# HandHeld_Terminal_V2.net
KiCad netlist of a schematic drawn in Altium Designer
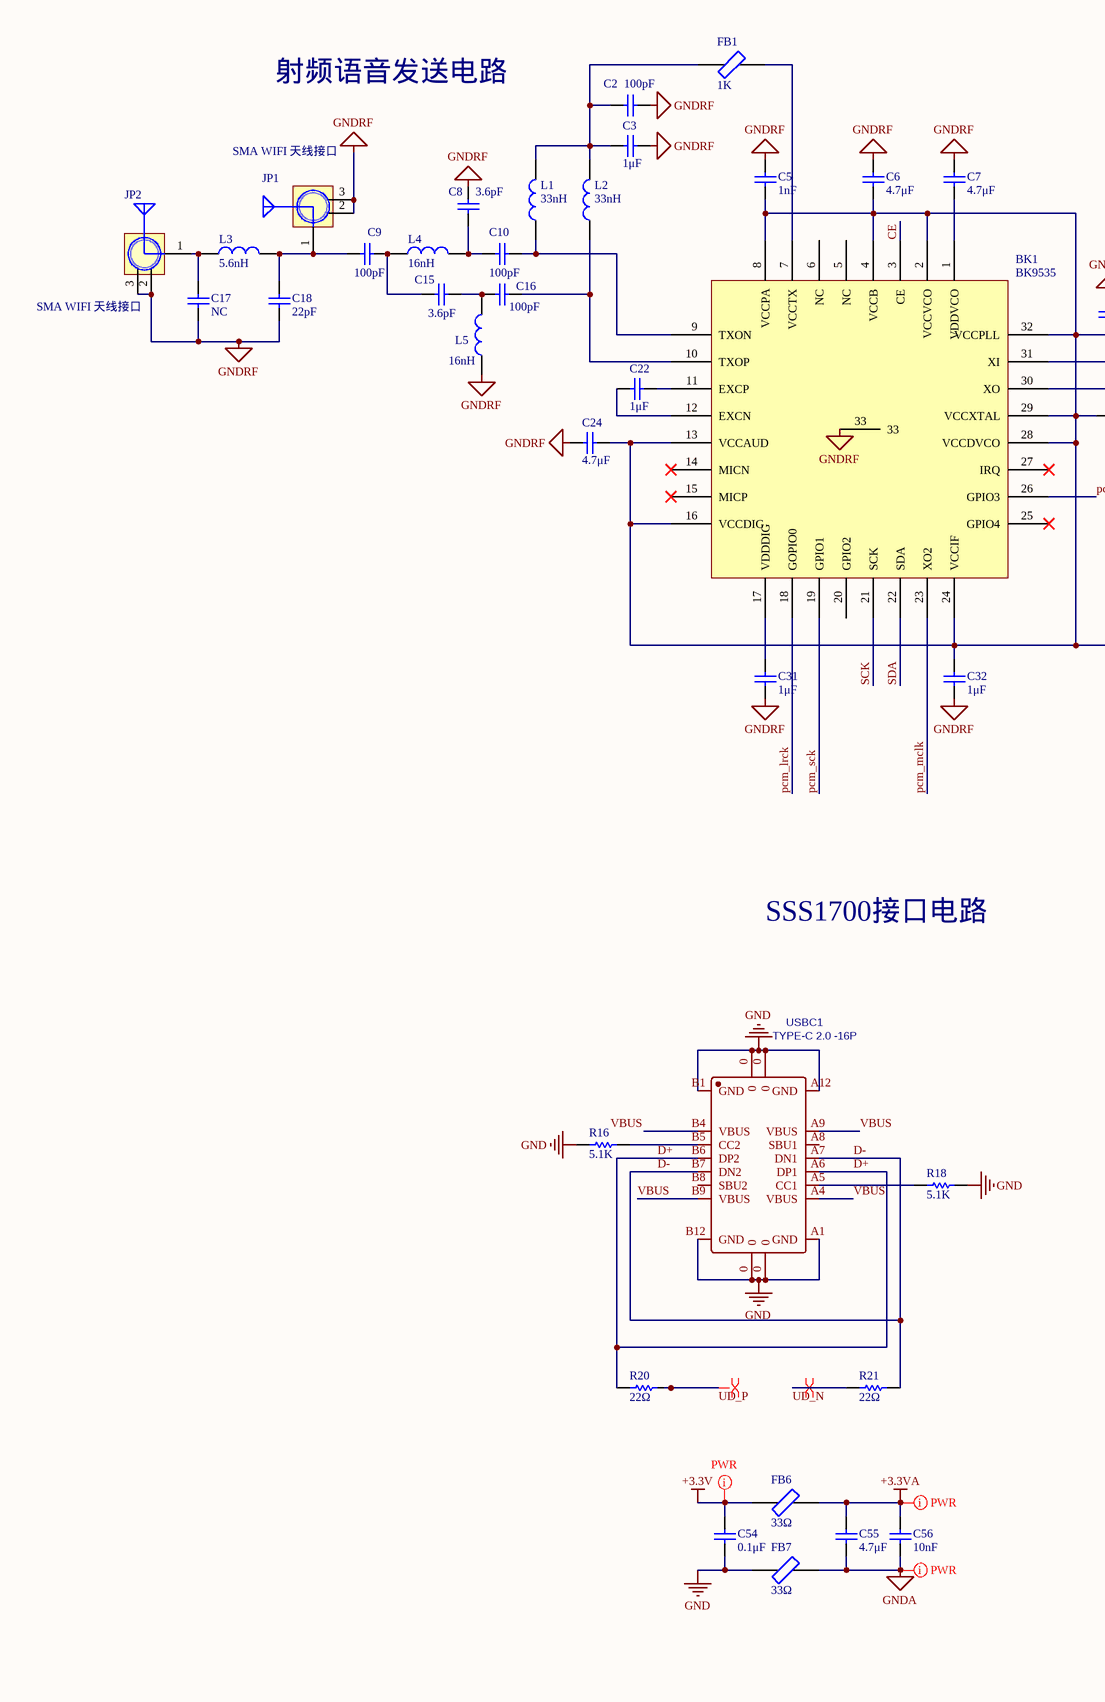
[diagram p0: HandHeld_Terminal_V2.SchDoc, left]
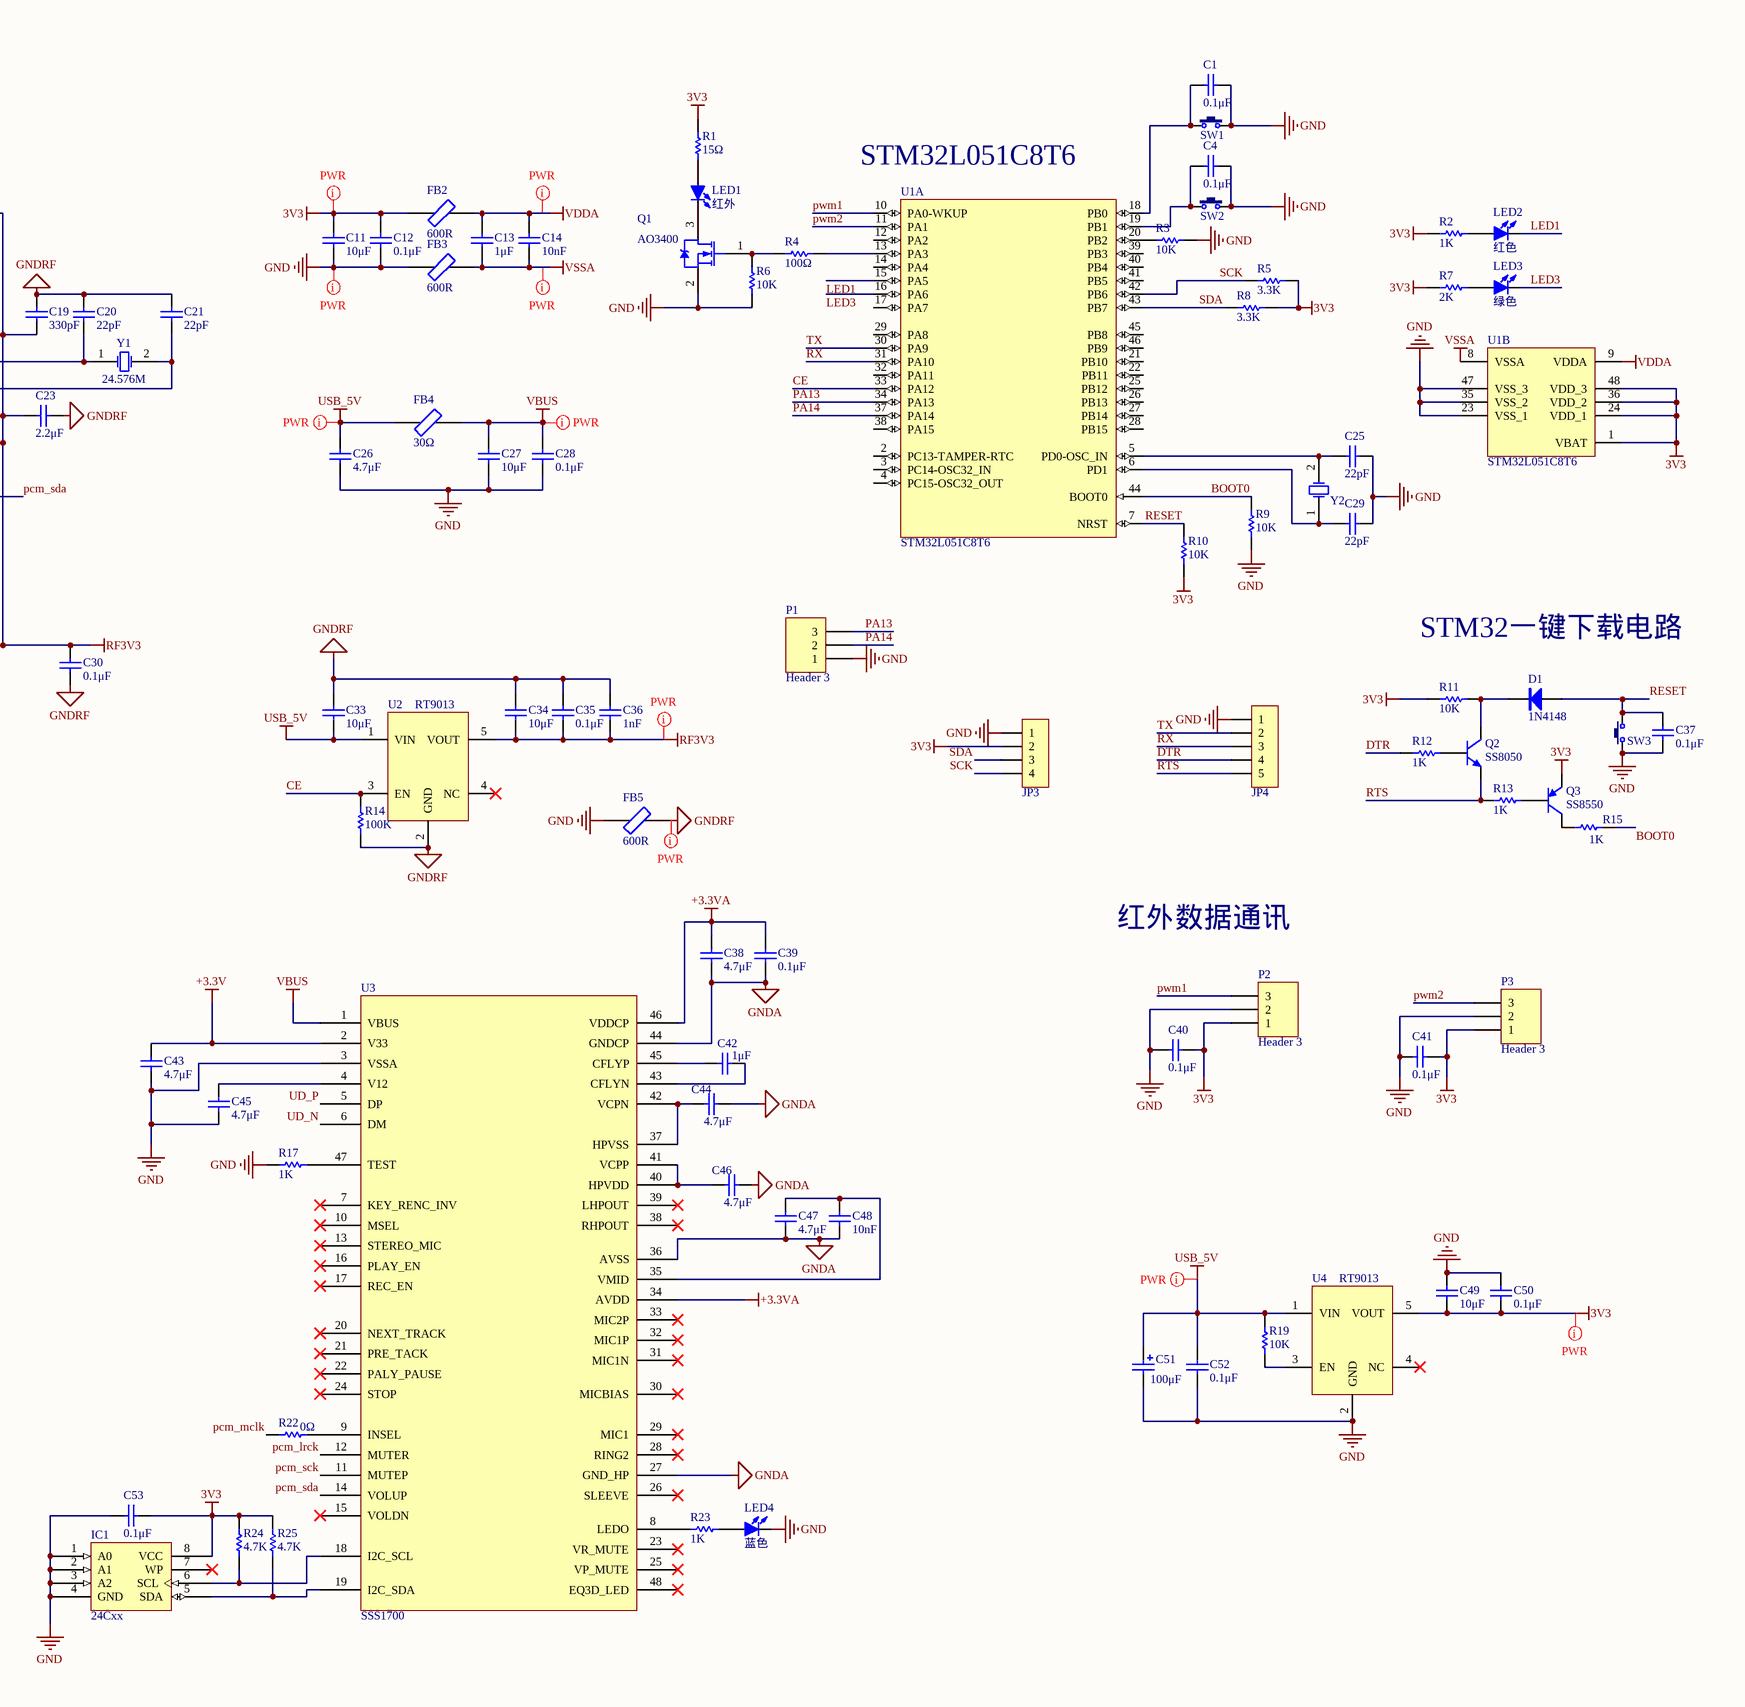
[diagram p1: HandHeld_Terminal_V2.SchDoc, right]

(export (version "E")
  (design (tool "Eeschema 10.0.6"))
  (components
    (comp (ref "BK1") (value "BK9535") (footprint "QFN32 5x5_N") (libsource (lib "Nixie") (part "BK9530")))
    (comp (ref "C1")
      (value "0.1μF")
      (footprint "C 0603_L")
      (description "Capacitor")
      (fields (field (name "Comment") "Cap") (field (name "PUBLISHER") "Altium Limited"))
      (libsource (lib "Nixie") (part "Cap"))
    )
    (comp (ref "C2")
      (value "100pF")
      (footprint "C 0603_L")
      (description "Capacitor")
      (fields (field (name "Comment") "Cap") (field (name "PUBLISHER") "Altium Limited"))
      (libsource (lib "Nixie") (part "Cap"))
    )
    (comp (ref "C3")
      (value "1μF")
      (footprint "C 0603_L")
      (description "Capacitor")
      (fields (field (name "Comment") "Cap") (field (name "PUBLISHER") "Altium Limited"))
      (libsource (lib "Nixie") (part "Cap"))
    )
    (comp (ref "C4")
      (value "0.1μF")
      (footprint "C 0603_L")
      (description "Capacitor")
      (fields (field (name "Comment") "Cap") (field (name "PUBLISHER") "Altium Limited"))
      (libsource (lib "Nixie") (part "Cap"))
    )
    (comp (ref "C5")
      (value "1nF")
      (footprint "C 0603_L")
      (description "Capacitor")
      (fields (field (name "Comment") "Cap") (field (name "PUBLISHER") "Altium Limited"))
      (libsource (lib "Nixie") (part "Cap"))
    )
    (comp (ref "C6")
      (value "4.7μF")
      (footprint "C 0603_L")
      (description "Capacitor")
      (fields (field (name "Comment") "Cap") (field (name "PUBLISHER") "Altium Limited"))
      (libsource (lib "Nixie") (part "Cap"))
    )
    (comp (ref "C7")
      (value "4.7μF")
      (footprint "C 0603_L")
      (description "Capacitor")
      (fields (field (name "Comment") "Cap") (field (name "PUBLISHER") "Altium Limited"))
      (libsource (lib "Nixie") (part "Cap"))
    )
    (comp (ref "C8")
      (value "3.6pF")
      (footprint "C 0603_L")
      (description "Capacitor")
      (fields (field (name "Comment") "Cap") (field (name "PUBLISHER") "Altium Limited"))
      (libsource (lib "Nixie") (part "Cap"))
    )
    (comp (ref "C9")
      (value "100pF")
      (footprint "C 0603_L")
      (description "Capacitor")
      (fields (field (name "Comment") "Cap") (field (name "PUBLISHER") "Altium Limited"))
      (libsource (lib "Nixie") (part "Cap"))
    )
    (comp (ref "C10")
      (value "100pF")
      (footprint "C 0603_L")
      (description "Capacitor")
      (fields (field (name "Comment") "Cap") (field (name "PUBLISHER") "Altium Limited"))
      (libsource (lib "Nixie") (part "Cap"))
    )
    (comp (ref "C11")
      (value "10μF")
      (footprint "C 0805_L")
      (description "Capacitor")
      (fields (field (name "Comment") "Cap") (field (name "PUBLISHER") "Altium Limited"))
      (libsource (lib "Nixie") (part "Cap"))
    )
    (comp (ref "C12")
      (value "0.1μF")
      (footprint "C 0603_L")
      (description "Capacitor")
      (fields (field (name "Comment") "Cap") (field (name "PUBLISHER") "Altium Limited"))
      (libsource (lib "Nixie") (part "Cap"))
    )
    (comp (ref "C13")
      (value "1μF")
      (footprint "C 0805_L")
      (description "Capacitor")
      (fields (field (name "Comment") "Cap") (field (name "PUBLISHER") "Altium Limited"))
      (libsource (lib "Nixie") (part "Cap"))
    )
    (comp (ref "C14")
      (value "10nF")
      (footprint "C 0805_L")
      (description "Capacitor")
      (fields (field (name "Comment") "Cap") (field (name "PUBLISHER") "Altium Limited"))
      (libsource (lib "Nixie") (part "Cap"))
    )
    (comp (ref "C15")
      (value "3.6pF")
      (footprint "C 0603_L")
      (description "Capacitor")
      (fields (field (name "Comment") "Cap") (field (name "PUBLISHER") "Altium Limited"))
      (libsource (lib "Nixie") (part "Cap"))
    )
    (comp (ref "C16")
      (value "100pF")
      (footprint "C 0603_L")
      (description "Capacitor")
      (fields (field (name "Comment") "Cap") (field (name "PUBLISHER") "Altium Limited"))
      (libsource (lib "Nixie") (part "Cap"))
    )
    (comp (ref "C17")
      (value "NC")
      (footprint "C 0603_L")
      (description "Capacitor")
      (fields (field (name "Comment") "Cap") (field (name "PUBLISHER") "Altium Limited"))
      (libsource (lib "Nixie") (part "Cap"))
    )
    (comp (ref "C18")
      (value "22pF")
      (footprint "C 0603_L")
      (description "Capacitor")
      (fields (field (name "Comment") "Cap") (field (name "PUBLISHER") "Altium Limited"))
      (libsource (lib "Nixie") (part "Cap"))
    )
    (comp (ref "C19")
      (value "330pF")
      (footprint "C 0603_L")
      (description "Capacitor")
      (fields (field (name "Comment") "Cap") (field (name "PUBLISHER") "Altium Limited"))
      (libsource (lib "Nixie") (part "Cap"))
    )
    (comp (ref "C20")
      (value "22pF")
      (footprint "C 0603_L")
      (description "Capacitor")
      (fields (field (name "Comment") "Cap") (field (name "PUBLISHER") "Altium Limited"))
      (libsource (lib "Nixie") (part "Cap"))
    )
    (comp (ref "C21")
      (value "22pF")
      (footprint "C 0603_L")
      (description "Capacitor")
      (fields (field (name "Comment") "Cap") (field (name "PUBLISHER") "Altium Limited"))
      (libsource (lib "Nixie") (part "Cap"))
    )
    (comp (ref "C22")
      (value "1μF")
      (footprint "C 0603_L")
      (description "Capacitor")
      (fields (field (name "Comment") "Cap") (field (name "PUBLISHER") "Altium Limited"))
      (libsource (lib "Nixie") (part "Cap"))
    )
    (comp (ref "C23")
      (value "2.2μF")
      (footprint "C 0603_L")
      (description "Capacitor")
      (fields (field (name "Comment") "Cap") (field (name "PUBLISHER") "Altium Limited"))
      (libsource (lib "Nixie") (part "Cap"))
    )
    (comp (ref "C24")
      (value "4.7μF")
      (footprint "C 0603_L")
      (description "Capacitor")
      (fields (field (name "Comment") "Cap") (field (name "PUBLISHER") "Altium Limited"))
      (libsource (lib "Nixie") (part "Cap"))
    )
    (comp (ref "C25")
      (value "22pF")
      (footprint "C 0603_L")
      (description "Capacitor")
      (fields (field (name "Comment") "Cap") (field (name "PUBLISHER") "Altium Limited"))
      (libsource (lib "Nixie") (part "Cap"))
    )
    (comp (ref "C26")
      (value "4.7μF")
      (footprint "C 0805_L")
      (description "Capacitor")
      (fields (field (name "Comment") "Cap") (field (name "PUBLISHER") "Altium Limited"))
      (libsource (lib "Nixie") (part "Cap"))
    )
    (comp (ref "C27")
      (value "10μF")
      (footprint "C 0805_L")
      (description "Capacitor")
      (fields (field (name "Comment") "Cap") (field (name "PUBLISHER") "Altium Limited"))
      (libsource (lib "Nixie") (part "Cap"))
    )
    (comp (ref "C28")
      (value "0.1μF")
      (footprint "C 0603_L")
      (description "Capacitor")
      (fields (field (name "Comment") "Cap") (field (name "PUBLISHER") "Altium Limited"))
      (libsource (lib "Nixie") (part "Cap"))
    )
    (comp (ref "C29")
      (value "22pF")
      (footprint "C 0603_L")
      (description "Capacitor")
      (fields (field (name "Comment") "Cap") (field (name "PUBLISHER") "Altium Limited"))
      (libsource (lib "Nixie") (part "Cap"))
    )
    (comp (ref "C30")
      (value "0.1μF")
      (footprint "C 0603_L")
      (description "Capacitor")
      (fields (field (name "Comment") "Cap") (field (name "PUBLISHER") "Altium Limited"))
      (libsource (lib "Nixie") (part "Cap"))
    )
    (comp (ref "C31")
      (value "1μF")
      (footprint "C 0603_L")
      (description "Capacitor")
      (fields (field (name "Comment") "Cap") (field (name "PUBLISHER") "Altium Limited"))
      (libsource (lib "Nixie") (part "Cap"))
    )
    (comp (ref "C32")
      (value "1μF")
      (footprint "C 0603_L")
      (description "Capacitor")
      (fields (field (name "Comment") "Cap") (field (name "PUBLISHER") "Altium Limited"))
      (libsource (lib "Nixie") (part "Cap"))
    )
    (comp (ref "C33")
      (value "10μF")
      (footprint "C 0805_L")
      (description "Capacitor")
      (fields (field (name "Comment") "Cap") (field (name "PUBLISHER") "Altium Limited"))
      (libsource (lib "Nixie") (part "Cap"))
    )
    (comp (ref "C34")
      (value "10μF")
      (footprint "C 0805_L")
      (description "Capacitor")
      (fields (field (name "Comment") "Cap") (field (name "PUBLISHER") "Altium Limited"))
      (libsource (lib "Nixie") (part "Cap"))
    )
    (comp (ref "C35")
      (value "0.1μF")
      (footprint "C 0603_L")
      (description "Capacitor")
      (fields (field (name "Comment") "Cap") (field (name "PUBLISHER") "Altium Limited"))
      (libsource (lib "Nixie") (part "Cap"))
    )
    (comp (ref "C36")
      (value "1nF")
      (footprint "C 0603_L")
      (description "Capacitor")
      (fields (field (name "Comment") "Cap") (field (name "PUBLISHER") "Altium Limited"))
      (libsource (lib "Nixie") (part "Cap"))
    )
    (comp (ref "C37")
      (value "0.1μF")
      (footprint "C 0603_L")
      (description "Capacitor")
      (fields (field (name "Comment") "Cap") (field (name "PUBLISHER") "Altium Limited"))
      (libsource (lib "Nixie") (part "Cap"))
    )
    (comp (ref "C38")
      (value "4.7μF")
      (footprint "C 0603_L")
      (description "Capacitor")
      (fields (field (name "Comment") "Cap") (field (name "PUBLISHER") "Altium Limited"))
      (libsource (lib "Nixie") (part "Cap"))
    )
    (comp (ref "C39")
      (value "0.1μF")
      (footprint "C 0603_L")
      (description "Capacitor")
      (fields (field (name "Comment") "Cap") (field (name "PUBLISHER") "Altium Limited"))
      (libsource (lib "Nixie") (part "Cap"))
    )
    (comp (ref "C40")
      (value "0.1μF")
      (footprint "C 0603_L")
      (description "Capacitor")
      (fields (field (name "Comment") "Cap") (field (name "PUBLISHER") "Altium Limited"))
      (libsource (lib "Nixie") (part "Cap"))
    )
    (comp (ref "C41")
      (value "0.1μF")
      (footprint "C 0603_L")
      (description "Capacitor")
      (fields (field (name "Comment") "Cap") (field (name "PUBLISHER") "Altium Limited"))
      (libsource (lib "Nixie") (part "Cap"))
    )
    (comp (ref "C42")
      (value "1μF")
      (footprint "C 0603_L")
      (description "Capacitor")
      (fields (field (name "Comment") "Cap") (field (name "PUBLISHER") "Altium Limited"))
      (libsource (lib "Nixie") (part "Cap"))
    )
    (comp (ref "C43")
      (value "4.7μF")
      (footprint "C 0603_L")
      (description "Capacitor")
      (fields (field (name "Comment") "Cap") (field (name "PUBLISHER") "Altium Limited"))
      (libsource (lib "Nixie") (part "Cap"))
    )
    (comp (ref "C44")
      (value "4.7μF")
      (footprint "C 0603_L")
      (description "Capacitor")
      (fields (field (name "Comment") "Cap") (field (name "PUBLISHER") "Altium Limited"))
      (libsource (lib "Nixie") (part "Cap"))
    )
    (comp (ref "C45")
      (value "4.7μF")
      (footprint "C 0603_L")
      (description "Capacitor")
      (fields (field (name "Comment") "Cap") (field (name "PUBLISHER") "Altium Limited"))
      (libsource (lib "Nixie") (part "Cap"))
    )
    (comp (ref "C46")
      (value "4.7μF")
      (footprint "C 0603_L")
      (description "Capacitor")
      (fields (field (name "Comment") "Cap") (field (name "PUBLISHER") "Altium Limited"))
      (libsource (lib "Nixie") (part "Cap"))
    )
    (comp (ref "C47")
      (value "4.7μF")
      (footprint "C 0603_L")
      (description "Capacitor")
      (fields (field (name "Comment") "Cap") (field (name "PUBLISHER") "Altium Limited"))
      (libsource (lib "Nixie") (part "Cap"))
    )
    (comp (ref "C48")
      (value "10nF")
      (footprint "C 0603_L")
      (description "Capacitor")
      (fields (field (name "Comment") "Cap") (field (name "PUBLISHER") "Altium Limited"))
      (libsource (lib "Nixie") (part "Cap"))
    )
    (comp (ref "C49")
      (value "10μF")
      (footprint "C 0805_L")
      (description "Capacitor")
      (fields (field (name "Comment") "Cap") (field (name "PUBLISHER") "Altium Limited"))
      (libsource (lib "Nixie") (part "Cap"))
    )
    (comp (ref "C50")
      (value "0.1μF")
      (footprint "C 0603_L")
      (description "Capacitor")
      (fields (field (name "Comment") "Cap") (field (name "PUBLISHER") "Altium Limited"))
      (libsource (lib "Nixie") (part "Cap"))
    )
    (comp (ref "C51")
      (value "100μF")
      (footprint "CM C(5*5.4)")
      (description "Polarized Capacitor (Radial)")
      (fields (field (name "Comment") "Cap Pol1") (field (name "PUBLISHER") "Altium Limited"))
      (libsource (lib "Nixie") (part "Cap Pol1"))
    )
    (comp (ref "C52")
      (value "0.1μF")
      (footprint "C 0603_L")
      (description "Capacitor")
      (fields (field (name "Comment") "Cap") (field (name "PUBLISHER") "Altium Limited"))
      (libsource (lib "Nixie") (part "Cap"))
    )
    (comp (ref "C53")
      (value "0.1μF")
      (footprint "C 0603_L")
      (description "Capacitor")
      (fields (field (name "Comment") "Cap") (field (name "PUBLISHER") "Altium Limited"))
      (libsource (lib "Nixie") (part "Cap"))
    )
    (comp (ref "C54")
      (value "0.1μF")
      (footprint "C 0603_L")
      (description "Capacitor")
      (fields (field (name "Comment") "Cap") (field (name "PUBLISHER") "Altium Limited"))
      (libsource (lib "Nixie") (part "Cap"))
    )
    (comp (ref "C55")
      (value "4.7μF")
      (footprint "C 0805_L")
      (description "Capacitor")
      (fields (field (name "Comment") "Cap") (field (name "PUBLISHER") "Altium Limited"))
      (libsource (lib "Nixie") (part "Cap"))
    )
    (comp (ref "C56")
      (value "10nF")
      (footprint "C 0603_L")
      (description "Capacitor")
      (fields (field (name "Comment") "Cap") (field (name "PUBLISHER") "Altium Limited"))
      (libsource (lib "Nixie") (part "Cap"))
    )
    (comp (ref "D1")
      (value "1N4148")
      (footprint "SOD-323")
      (description "开关二极管")
      (libsource (lib "Nixie") (part "1N4148"))
    )
    (comp (ref "FB1")
      (value "1K")
      (footprint "C 0603_L")
      (description "铁氧体磁珠")
      (fields (field (name "Comment") "Ferrite bead"))
      (libsource (lib "Nixie") (part "Ferrite bead"))
    )
    (comp (ref "FB2")
      (value "600R")
      (footprint "C 0603_L")
      (description "铁氧体磁珠")
      (fields (field (name "Comment") "Ferrite bead"))
      (libsource (lib "Nixie") (part "Ferrite bead"))
    )
    (comp (ref "FB3")
      (value "600R")
      (footprint "C 0603_L")
      (description "铁氧体磁珠")
      (fields (field (name "Comment") "Ferrite bead"))
      (libsource (lib "Nixie") (part "Ferrite bead"))
    )
    (comp (ref "FB4")
      (value "30Ω")
      (footprint "C 0603_L")
      (description "铁氧体磁珠")
      (fields (field (name "Comment") "Ferrite bead"))
      (libsource (lib "Nixie") (part "Ferrite bead"))
    )
    (comp (ref "FB5")
      (value "600R")
      (footprint "C 0805_L")
      (description "铁氧体磁珠")
      (fields (field (name "Comment") "Ferrite bead"))
      (libsource (lib "Nixie") (part "Ferrite bead"))
    )
    (comp (ref "FB6")
      (value "33Ω")
      (footprint "C 0603_L")
      (description "铁氧体磁珠")
      (fields (field (name "Comment") "Ferrite bead"))
      (libsource (lib "Nixie") (part "Ferrite bead"))
    )
    (comp (ref "FB7")
      (value "33Ω")
      (footprint "C 0603_L")
      (description "铁氧体磁珠")
      (fields (field (name "Comment") "Ferrite bead"))
      (libsource (lib "Nixie") (part "Ferrite bead"))
    )
    (comp (ref "IC1")
      (value "24Cxx")
      (footprint "SOP8_L")
      (description "外置EEPROM")
      (fields (field (name "版权归属") "封装库来自淘宝 ID：黄晶宝石"))
      (libsource (lib "Nixie") (part "24Cxx"))
    )
    (comp (ref "JP1")
      (value "SMA WIFI 天线接口")
      (footprint "COAXIAL/SMD/CON/V/I-PEX/W08-5801")
      (description "SMA-2.4G射频天线接口")
      (fields (field (name "版权归属") "封装库来自淘宝 ID：黄晶宝石"))
      (libsource (lib "Nixie") (part "SMA"))
    )
    (comp (ref "JP2")
      (value "SMA WIFI 天线接口")
      (footprint "SMA-KE")
      (description "SMA-2.4G射频天线接口")
      (fields (field (name "版权归属") "封装库来自淘宝 ID：黄晶宝石"))
      (libsource (lib "") (part "SMA_1"))
    )
    (comp (ref "JP3")
      (value "HDR-1X4")
      (footprint "HDR2.54-LI-4P")
      (description "4P接插件")
      (fields (field (name "版权归属") "封装库来自淘宝 ID：黄晶宝石"))
      (libsource (lib "Nixie") (part "Header 4"))
    )
    (comp (ref "JP4")
      (value "HDR-1X5")
      (footprint "HDR2.0-LI-5P")
      (description "5P接插件")
      (fields (field (name "版权归属") "封装库来自淘宝 ID：黄晶宝石"))
      (libsource (lib "Nixie") (part "Header 5"))
    )
    (comp (ref "L1")
      (value "33nH")
      (footprint "L 0603")
      (description "小功率贴片电感")
      (fields (field (name "Comment") "L"))
      (libsource (lib "Nixie") (part "L"))
    )
    (comp (ref "L2")
      (value "33nH")
      (footprint "L 0603")
      (description "小功率贴片电感")
      (fields (field (name "Comment") "L"))
      (libsource (lib "Nixie") (part "L"))
    )
    (comp (ref "L3")
      (value "5.6nH")
      (footprint "L 0603")
      (description "小功率贴片电感")
      (fields (field (name "Comment") "L"))
      (libsource (lib "Nixie") (part "L"))
    )
    (comp (ref "L4")
      (value "16nH")
      (footprint "L 0603")
      (description "小功率贴片电感")
      (fields (field (name "Comment") "L"))
      (libsource (lib "Nixie") (part "L"))
    )
    (comp (ref "L5")
      (value "16nH")
      (footprint "L 0603")
      (description "小功率贴片电感")
      (fields (field (name "Comment") "L"))
      (libsource (lib "Nixie") (part "L"))
    )
    (comp (ref "LED1")
      (value "红外")
      (footprint "LED 3MM-R")
      (description "贴片LED")
      (fields (field (name "版权归属") "封装库来自淘宝 ID：黄晶宝石"))
      (libsource (lib "Nixie") (part "LED-SMD"))
    )
    (comp (ref "LED2")
      (value "红色")
      (footprint "LED 0805R")
      (description "贴片LED")
      (fields (field (name "版权归属") "封装库来自淘宝 ID：黄晶宝石"))
      (libsource (lib "Nixie") (part "LED-SMD"))
    )
    (comp (ref "LED3")
      (value "绿色")
      (footprint "LED 0805G")
      (description "贴片LED")
      (fields (field (name "版权归属") "封装库来自淘宝 ID：黄晶宝石"))
      (libsource (lib "Nixie") (part "LED-SMD"))
    )
    (comp (ref "LED4")
      (value "蓝色")
      (footprint "LED 0805B")
      (description "贴片LED")
      (fields (field (name "版权归属") "封装库来自淘宝 ID：黄晶宝石"))
      (libsource (lib "Nixie") (part "LED-SMD"))
    )
    (comp (ref "P1")
      (value "Header 3")
      (footprint "HDR2.54-LI-3P")
      (description "Header, 3-Pin")
      (fields (field (name "PUBLISHER") "Altium Limited"))
      (libsource (lib "Miscellaneous Connectors") (part "Header 3"))
    )
    (comp (ref "P2")
      (value "Header 3")
      (footprint "HDR1X3")
      (description "Header, 3-Pin")
      (fields (field (name "PUBLISHER") "Altium Limited"))
      (libsource (lib "") (part "Header 3_1"))
    )
    (comp (ref "P3")
      (value "Header 3")
      (footprint "HDR1X3")
      (description "Header, 3-Pin")
      (fields (field (name "PUBLISHER") "Altium Limited"))
      (libsource (lib "") (part "Header 3_1"))
    )
    (comp (ref "Q1")
      (value "AO3400")
      (footprint "SOT-23-3L")
      (description "N-Channel Power MOSFET")
      (fields (field (name "PUBLISHER") "Altium Limited"))
      (libsource (lib "Nixie") (part "NMOS-2"))
    )
    (comp (ref "Q2")
      (value "SS8050")
      (footprint "SOT-23-3L")
      (description "高频放大-NPN型")
      (fields (field (name "版权归属") "封装库来自淘宝 ID：黄晶宝石"))
      (libsource (lib "Nixie") (part "8050-SMD"))
    )
    (comp (ref "Q3")
      (value "SS8550")
      (footprint "SOT-23-3L")
      (description "高频放大-PNP型")
      (fields (field (name "版权归属") "封装库来自淘宝 ID：黄晶宝石"))
      (libsource (lib "Nixie") (part "8550-SMD"))
    )
    (comp (ref "R1")
      (value "15Ω")
      (footprint "R 1206_L")
      (description "Resistor")
      (fields (field (name "PUBLISHER") "Altium Limited"))
      (libsource (lib "Nixie") (part "Resistor"))
    )
    (comp (ref "R2")
      (value "1K")
      (footprint "R 0603_L")
      (description "Resistor")
      (fields (field (name "PUBLISHER") "Altium Limited"))
      (libsource (lib "Nixie") (part "Resistor"))
    )
    (comp (ref "R3")
      (value "10K")
      (footprint "R 0603_L")
      (description "Resistor")
      (fields (field (name "PUBLISHER") "Altium Limited"))
      (libsource (lib "Nixie") (part "Resistor"))
    )
    (comp (ref "R4")
      (value "100Ω")
      (footprint "R 0603_L")
      (description "Resistor")
      (fields (field (name "PUBLISHER") "Altium Limited"))
      (libsource (lib "Nixie") (part "Resistor"))
    )
    (comp (ref "R5")
      (value "3.3K")
      (footprint "R 0603_L")
      (description "Resistor")
      (fields (field (name "PUBLISHER") "Altium Limited"))
      (libsource (lib "Nixie") (part "Resistor"))
    )
    (comp (ref "R6")
      (value "10K")
      (footprint "R 0603_L")
      (description "Resistor")
      (fields (field (name "PUBLISHER") "Altium Limited"))
      (libsource (lib "Nixie") (part "Resistor"))
    )
    (comp (ref "R7")
      (value "2K")
      (footprint "R 0603_L")
      (description "Resistor")
      (fields (field (name "PUBLISHER") "Altium Limited"))
      (libsource (lib "Nixie") (part "Resistor"))
    )
    (comp (ref "R8")
      (value "3.3K")
      (footprint "R 0603_L")
      (description "Resistor")
      (fields (field (name "PUBLISHER") "Altium Limited"))
      (libsource (lib "Nixie") (part "Resistor"))
    )
    (comp (ref "R9")
      (value "10K")
      (footprint "R 0603_L")
      (description "Resistor")
      (fields (field (name "PUBLISHER") "Altium Limited"))
      (libsource (lib "Nixie") (part "Resistor"))
    )
    (comp (ref "R10")
      (value "10K")
      (footprint "R 0603_L")
      (description "Resistor")
      (fields (field (name "PUBLISHER") "Altium Limited"))
      (libsource (lib "Nixie") (part "Resistor"))
    )
    (comp (ref "R11")
      (value "10K")
      (footprint "R 0603_L")
      (description "Resistor")
      (fields (field (name "PUBLISHER") "Altium Limited"))
      (libsource (lib "Nixie") (part "Resistor"))
    )
    (comp (ref "R12")
      (value "1K")
      (footprint "R 0603_L")
      (description "Resistor")
      (fields (field (name "PUBLISHER") "Altium Limited"))
      (libsource (lib "Nixie") (part "Resistor"))
    )
    (comp (ref "R13")
      (value "1K")
      (footprint "R 0603_L")
      (description "Resistor")
      (fields (field (name "PUBLISHER") "Altium Limited"))
      (libsource (lib "Nixie") (part "Resistor"))
    )
    (comp (ref "R14")
      (value "100K")
      (footprint "R 0603_L")
      (description "Resistor")
      (fields (field (name "PUBLISHER") "Altium Limited"))
      (libsource (lib "Nixie") (part "Resistor"))
    )
    (comp (ref "R15")
      (value "1K")
      (footprint "R 0603_L")
      (description "Resistor")
      (fields (field (name "PUBLISHER") "Altium Limited"))
      (libsource (lib "Nixie") (part "Resistor"))
    )
    (comp (ref "R16")
      (value "5.1K")
      (footprint "R 0603_L")
      (description "Resistor")
      (fields (field (name "PUBLISHER") "Altium Limited"))
      (libsource (lib "Nixie") (part "Resistor"))
    )
    (comp (ref "R17")
      (value "1K")
      (footprint "R 0603_L")
      (description "Resistor")
      (fields (field (name "PUBLISHER") "Altium Limited"))
      (libsource (lib "Nixie") (part "Resistor"))
    )
    (comp (ref "R18")
      (value "5.1K")
      (footprint "R 0603_L")
      (description "Resistor")
      (fields (field (name "PUBLISHER") "Altium Limited"))
      (libsource (lib "Nixie") (part "Resistor"))
    )
    (comp (ref "R19")
      (value "10K")
      (footprint "R 0603_L")
      (description "Resistor")
      (fields (field (name "PUBLISHER") "Altium Limited"))
      (libsource (lib "Nixie") (part "Resistor"))
    )
    (comp (ref "R20")
      (value "22Ω")
      (footprint "R 0603_L")
      (description "Resistor")
      (fields (field (name "PUBLISHER") "Altium Limited"))
      (libsource (lib "Nixie") (part "Resistor"))
    )
    (comp (ref "R21")
      (value "22Ω")
      (footprint "R 0603_L")
      (description "Resistor")
      (fields (field (name "PUBLISHER") "Altium Limited"))
      (libsource (lib "Nixie") (part "Resistor"))
    )
    (comp (ref "R22")
      (value "0Ω")
      (footprint "R 0603_L")
      (description "Resistor")
      (fields (field (name "PUBLISHER") "Altium Limited"))
      (libsource (lib "Nixie") (part "Resistor"))
    )
    (comp (ref "R23")
      (value "1K")
      (footprint "R 0603_L")
      (description "Resistor")
      (fields (field (name "PUBLISHER") "Altium Limited"))
      (libsource (lib "Nixie") (part "Resistor"))
    )
    (comp (ref "R24")
      (value "4.7K")
      (footprint "R 0603_L")
      (description "Resistor")
      (fields (field (name "PUBLISHER") "Altium Limited"))
      (libsource (lib "Nixie") (part "Resistor"))
    )
    (comp (ref "R25")
      (value "4.7K")
      (footprint "R 0603_L")
      (description "Resistor")
      (fields (field (name "PUBLISHER") "Altium Limited"))
      (libsource (lib "Nixie") (part "Resistor"))
    )
    (comp (ref "SW1")
      (value "3x6x5")
      (footprint "TSW SMD-3*6*2.5")
      (description "3x6轻触开关")
      (fields (field (name "版权归属") "封装库来自淘宝 ID：黄晶宝石"))
      (libsource (lib "Nixie") (part "TSW 3x6"))
    )
    (comp (ref "SW2")
      (value "3x6x5")
      (footprint "TSW SMD-3*6*2.5")
      (description "3x6轻触开关")
      (fields (field (name "版权归属") "封装库来自淘宝 ID：黄晶宝石"))
      (libsource (lib "Nixie") (part "TSW 3x6"))
    )
    (comp (ref "SW3")
      (value "3x6x5")
      (footprint "TSW SMD-3*6*2.5")
      (description "3x6轻触开关")
      (fields (field (name "版权归属") "封装库来自淘宝 ID：黄晶宝石"))
      (libsource (lib "") (part "TSW 3x6_1"))
    )
    (comp (ref "U1")
      (value "STM32L051C8T6")
      (footprint "LQFP48_L")
      (description "ARM")
      (libsource (lib "Nixie") (part "STM32F103C8T6"))
    )
    (comp (ref "U2")
      (value "RT9013")
      (footprint "SOT23-5L")
      (description "LDO")
      (libsource (lib "HandHeld_terminal") (part "RT9013"))
    )
    (comp (ref "U3")
      (value "SSS1700")
      (footprint "LQFP48_L")
      (description "USB音频芯片")
      (libsource (lib "Nixie") (part "SSS1700"))
    )
    (comp (ref "U4")
      (value "RT9013")
      (footprint "SOT23-5L")
      (description "LDO")
      (libsource (lib "HandHeld_terminal") (part "RT9013"))
    )
    (comp (ref "USBC1")
      (value "TYPE-C 2.0 -16P")
      (footprint "USB-C-SMD_TYPE-C-USB-5")
      (description "USB2.0 Type-C 母座 16Pin")
      (libsource (lib "Nixie") (part "USB2.0 Type-C 16Pin母座"))
    )
    (comp (ref "Y1")
      (value "24.576M")
      (footprint "OSC 5032-2P")
      (description "Crystal Oscillator")
      (fields (field (name "PUBLISHER") "Altium Limited"))
      (libsource (lib "Miscellaneous Devices") (part "XTAL"))
    )
    (comp (ref "Y2")
      (value "8MHz ±20ppm 20pF")
      (footprint "OSC 5032-2P")
      (description "贴片晶振")
      (libsource (lib "HandHeld_terminal") (part "SMD-5032_2P 8MHz 20ppm 20pF"))
    )
  )
  (nets
    (net (code "1") (name "+3.3V") (class "Default")
      (node (ref "C43") (pin "2") (pinfunction "2_2") (pintype "passive"))
      (node (ref "C54") (pin "2") (pinfunction "2_2") (pintype "passive"))
      (node (ref "FB6") (pin "1") (pinfunction "1_1") (pintype "passive"))
      (node (ref "U3") (pin "2") (pinfunction "V33_2") (pintype "passive"))
    )
    (net (code "2") (name "+3.3VA") (class "Default")
      (node (ref "C38") (pin "2") (pinfunction "2_2") (pintype "passive"))
      (node (ref "C39") (pin "2") (pinfunction "2_2") (pintype "passive"))
      (node (ref "C55") (pin "2") (pinfunction "2_2") (pintype "passive"))
      (node (ref "C56") (pin "2") (pinfunction "2_2") (pintype "passive"))
      (node (ref "FB6") (pin "2") (pinfunction "2_2") (pintype "passive"))
      (node (ref "U3") (pin "34") (pinfunction "AVDD_34") (pintype "passive"))
      (node (ref "U3") (pin "46") (pinfunction "VDDCP_46") (pintype "passive"))
    )
    (net (code "3") (name "/BOOT0") (class "Default")
      (node (ref "R15") (pin "2") (pinfunction "2_2") (pintype "passive"))
      (node (ref "R9") (pin "1") (pinfunction "1_1") (pintype "passive"))
      (node (ref "U1") (pin "44") (pinfunction "BOOT0_44") (pintype "input"))
    )
    (net (code "4") (name "/CE") (class "Default")
      (node (ref "BK1") (pin "3") (pinfunction "CE_3") (pintype "passive"))
      (node (ref "R14") (pin "2") (pinfunction "2_2") (pintype "passive"))
      (node (ref "U1") (pin "33") (pinfunction "PA12_33") (pintype "bidirectional"))
      (node (ref "U2") (pin "3") (pinfunction "EN_3") (pintype "passive"))
    )
    (net (code "5") (name "/D+") (class "Default")
      (node (ref "R20") (pin "1") (pinfunction "1_1") (pintype "passive"))
      (node (ref "USBC1") (pin "A6") (pinfunction "DP1_A6") (pintype "passive"))
      (node (ref "USBC1") (pin "B6") (pinfunction "DP2_B6") (pintype "passive"))
    )
    (net (code "6") (name "/D-") (class "Default")
      (node (ref "R21") (pin "2") (pinfunction "2_2") (pintype "passive"))
      (node (ref "USBC1") (pin "A7") (pinfunction "DN1_A7") (pintype "passive"))
      (node (ref "USBC1") (pin "B7") (pinfunction "DN2_B7") (pintype "passive"))
    )
    (net (code "7") (name "/DTR") (class "Default")
      (node (ref "JP4") (pin "4") (pinfunction "4_4") (pintype "passive"))
      (node (ref "R12") (pin "1") (pinfunction "1_1") (pintype "passive"))
    )
    (net (code "8") (name "/LED1") (class "Default")
      (node (ref "LED2") (pin "2") (pinfunction "K_2") (pintype "passive"))
      (node (ref "U1") (pin "15") (pinfunction "PA5_15") (pintype "bidirectional"))
    )
    (net (code "9") (name "/LED3") (class "Default")
      (node (ref "LED3") (pin "2") (pinfunction "K_2") (pintype "passive"))
      (node (ref "U1") (pin "16") (pinfunction "PA6_16") (pintype "bidirectional"))
    )
    (net (code "10") (name "/PA13") (class "Default")
      (node (ref "P1") (pin "3") (pinfunction "3_3") (pintype "passive"))
      (node (ref "U1") (pin "34") (pinfunction "PA13_34") (pintype "bidirectional"))
    )
    (net (code "11") (name "/PA14") (class "Default")
      (node (ref "P1") (pin "2") (pinfunction "2_2") (pintype "passive"))
      (node (ref "U1") (pin "37") (pinfunction "PA14_37") (pintype "bidirectional"))
    )
    (net (code "12") (name "/RESET") (class "Default")
      (node (ref "C37") (pin "2") (pinfunction "2_2") (pintype "passive"))
      (node (ref "D1") (pin "1") (pinfunction "A_1") (pintype "passive"))
      (node (ref "R10") (pin "1") (pinfunction "1_1") (pintype "passive"))
      (node (ref "SW3") (pin "2") (pinfunction "2_2") (pintype "passive"))
      (node (ref "U1") (pin "7") (pinfunction "NRST_7") (pintype "bidirectional"))
    )
    (net (code "13") (name "/RTS") (class "Default")
      (node (ref "JP4") (pin "5") (pinfunction "5_5") (pintype "passive"))
      (node (ref "Q2") (pin "2") (pinfunction "E_2") (pintype "passive"))
      (node (ref "R13") (pin "1") (pinfunction "1_1") (pintype "passive"))
    )
    (net (code "14") (name "/RX") (class "Default")
      (node (ref "JP4") (pin "3") (pinfunction "3_3") (pintype "passive"))
      (node (ref "U1") (pin "31") (pinfunction "PA10_31") (pintype "bidirectional"))
    )
    (net (code "15") (name "/SCK") (class "Default")
      (node (ref "BK1") (pin "21") (pinfunction "SCK_21") (pintype "passive"))
      (node (ref "JP3") (pin "4") (pinfunction "4_4") (pintype "passive"))
      (node (ref "R5") (pin "2") (pinfunction "2_2") (pintype "passive"))
      (node (ref "U1") (pin "42") (pinfunction "PB6_42") (pintype "bidirectional"))
    )
    (net (code "16") (name "/SDA") (class "Default")
      (node (ref "BK1") (pin "22") (pinfunction "SDA_22") (pintype "passive"))
      (node (ref "JP3") (pin "3") (pinfunction "3_3") (pintype "passive"))
      (node (ref "R8") (pin "2") (pinfunction "2_2") (pintype "passive"))
      (node (ref "U1") (pin "43") (pinfunction "PB7_43") (pintype "bidirectional"))
    )
    (net (code "17") (name "/TX") (class "Default")
      (node (ref "JP4") (pin "2") (pinfunction "2_2") (pintype "passive"))
      (node (ref "U1") (pin "30") (pinfunction "PA9_30") (pintype "bidirectional"))
    )
    (net (code "18") (name "/UD_N") (class "Default")
      (node (ref "R21") (pin "1") (pinfunction "1_1") (pintype "passive"))
      (node (ref "U3") (pin "6") (pinfunction "DM_6") (pintype "passive"))
    )
    (net (code "19") (name "/UD_P") (class "Default")
      (node (ref "R20") (pin "2") (pinfunction "2_2") (pintype "passive"))
      (node (ref "U3") (pin "5") (pinfunction "DP_5") (pintype "passive"))
    )
    (net (code "20") (name "/pcm_lrck") (class "Default")
      (node (ref "BK1") (pin "18") (pinfunction "GOPIO0_18") (pintype "passive"))
      (node (ref "U3") (pin "12") (pinfunction "MUTER_12") (pintype "passive"))
    )
    (net (code "21") (name "/pcm_mclk") (class "Default")
      (node (ref "BK1") (pin "23") (pinfunction "XO2_23") (pintype "passive"))
      (node (ref "R22") (pin "2") (pinfunction "2_2") (pintype "passive"))
    )
    (net (code "22") (name "/pcm_sck") (class "Default")
      (node (ref "BK1") (pin "19") (pinfunction "GPIO1_19") (pintype "passive"))
      (node (ref "U3") (pin "11") (pinfunction "MUTEP_11") (pintype "passive"))
    )
    (net (code "23") (name "/pcm_sda") (class "Default")
      (node (ref "BK1") (pin "26") (pinfunction "GPIO3_26") (pintype "passive"))
      (node (ref "U3") (pin "14") (pinfunction "VOLUP_14") (pintype "passive"))
    )
    (net (code "24") (name "/pwm1") (class "Default")
      (node (ref "P2") (pin "3") (pinfunction "3_3") (pintype "passive"))
      (node (ref "U1") (pin "10") (pinfunction "PA0-WKUP_10") (pintype "bidirectional"))
    )
    (net (code "25") (name "/pwm2") (class "Default")
      (node (ref "P3") (pin "3") (pinfunction "3_3") (pintype "passive"))
      (node (ref "U1") (pin "11") (pinfunction "PA1_11") (pintype "bidirectional"))
    )
    (net (code "26") (name "3V3") (class "Default")
      (node (ref "C11") (pin "2") (pinfunction "2_2") (pintype "passive"))
      (node (ref "C12") (pin "2") (pinfunction "2_2") (pintype "passive"))
      (node (ref "C40") (pin "1") (pinfunction "1_1") (pintype "passive"))
      (node (ref "C41") (pin "1") (pinfunction "1_1") (pintype "passive"))
      (node (ref "C49") (pin "1") (pinfunction "1_1") (pintype "passive"))
      (node (ref "C50") (pin "2") (pinfunction "2_2") (pintype "passive"))
      (node (ref "C53") (pin "1") (pinfunction "1_1") (pintype "passive"))
      (node (ref "FB2") (pin "1") (pinfunction "1_1") (pintype "passive"))
      (node (ref "IC1") (pin "8") (pinfunction "VCC_8") (pintype "power_in"))
      (node (ref "JP3") (pin "2") (pinfunction "2_2") (pintype "passive"))
      (node (ref "P2") (pin "1") (pinfunction "1_1") (pintype "passive"))
      (node (ref "P3") (pin "1") (pinfunction "1_1") (pintype "passive"))
      (node (ref "Q3") (pin "2") (pinfunction "E_2") (pintype "passive"))
      (node (ref "R1") (pin "2") (pinfunction "2_2") (pintype "passive"))
      (node (ref "R10") (pin "2") (pinfunction "2_2") (pintype "passive"))
      (node (ref "R11") (pin "1") (pinfunction "1_1") (pintype "passive"))
      (node (ref "R2") (pin "2") (pinfunction "2_2") (pintype "passive"))
      (node (ref "R24") (pin "2") (pinfunction "2_2") (pintype "passive"))
      (node (ref "R25") (pin "2") (pinfunction "2_2") (pintype "passive"))
      (node (ref "R5") (pin "1") (pinfunction "1_1") (pintype "passive"))
      (node (ref "R7") (pin "2") (pinfunction "2_2") (pintype "passive"))
      (node (ref "R8") (pin "1") (pinfunction "1_1") (pintype "passive"))
      (node (ref "U1") (pin "1") (pinfunction "VBAT_1") (pintype "power_in"))
      (node (ref "U1") (pin "24") (pinfunction "VDD_1_24") (pintype "power_in"))
      (node (ref "U1") (pin "36") (pinfunction "VDD_2_36") (pintype "power_in"))
      (node (ref "U1") (pin "48") (pinfunction "VDD_3_48") (pintype "power_in"))
      (node (ref "U4") (pin "5") (pinfunction "VOUT_5") (pintype "passive"))
    )
    (net (code "27") (name "GND") (class "Default")
      (node (ref "C1") (pin "1") (pinfunction "1_1") (pintype "passive"))
      (node (ref "C11") (pin "1") (pinfunction "1_1") (pintype "passive"))
      (node (ref "C12") (pin "1") (pinfunction "1_1") (pintype "passive"))
      (node (ref "C25") (pin "1") (pinfunction "1_1") (pintype "passive"))
      (node (ref "C26") (pin "1") (pinfunction "1_1") (pintype "passive"))
      (node (ref "C27") (pin "1") (pinfunction "1_1") (pintype "passive"))
      (node (ref "C28") (pin "1") (pinfunction "1_1") (pintype "passive"))
      (node (ref "C29") (pin "1") (pinfunction "1_1") (pintype "passive"))
      (node (ref "C37") (pin "1") (pinfunction "1_1") (pintype "passive"))
      (node (ref "C4") (pin "1") (pinfunction "1_1") (pintype "passive"))
      (node (ref "C40") (pin "2") (pinfunction "2_2") (pintype "passive"))
      (node (ref "C41") (pin "2") (pinfunction "2_2") (pintype "passive"))
      (node (ref "C43") (pin "1") (pinfunction "1_1") (pintype "passive"))
      (node (ref "C45") (pin "1") (pinfunction "1_1") (pintype "passive"))
      (node (ref "C49") (pin "2") (pinfunction "2_2") (pintype "passive"))
      (node (ref "C50") (pin "1") (pinfunction "1_1") (pintype "passive"))
      (node (ref "C51") (pin "2") (pinfunction "2_2") (pintype "passive"))
      (node (ref "C52") (pin "2") (pinfunction "2_2") (pintype "passive"))
      (node (ref "C53") (pin "2") (pinfunction "2_2") (pintype "passive"))
      (node (ref "C54") (pin "1") (pinfunction "1_1") (pintype "passive"))
      (node (ref "FB3") (pin "1") (pinfunction "1_1") (pintype "passive"))
      (node (ref "FB5") (pin "1") (pinfunction "1_1") (pintype "passive"))
      (node (ref "FB7") (pin "1") (pinfunction "1_1") (pintype "passive"))
      (node (ref "IC1") (pin "1") (pinfunction "A0_1") (pintype "input"))
      (node (ref "IC1") (pin "2") (pinfunction "A1_2") (pintype "input"))
      (node (ref "IC1") (pin "3") (pinfunction "A2_3") (pintype "input"))
      (node (ref "IC1") (pin "4") (pinfunction "GND_4") (pintype "passive"))
      (node (ref "JP3") (pin "1") (pinfunction "1_1") (pintype "passive"))
      (node (ref "JP4") (pin "1") (pinfunction "1_1") (pintype "passive"))
      (node (ref "LED4") (pin "2") (pinfunction "K_2") (pintype "passive"))
      (node (ref "P1") (pin "1") (pinfunction "1_1") (pintype "passive"))
      (node (ref "P2") (pin "2") (pinfunction "2_2") (pintype "passive"))
      (node (ref "P3") (pin "2") (pinfunction "2_2") (pintype "passive"))
      (node (ref "Q1") (pin "2") (pinfunction "S_2") (pintype "passive"))
      (node (ref "R16") (pin "2") (pinfunction "2_2") (pintype "passive"))
      (node (ref "R17") (pin "2") (pinfunction "2_2") (pintype "passive"))
      (node (ref "R18") (pin "1") (pinfunction "1_1") (pintype "passive"))
      (node (ref "R3") (pin "2") (pinfunction "2_2") (pintype "passive"))
      (node (ref "R6") (pin "1") (pinfunction "1_1") (pintype "passive"))
      (node (ref "R9") (pin "2") (pinfunction "2_2") (pintype "passive"))
      (node (ref "SW1") (pin "2") (pinfunction "2_2") (pintype "passive"))
      (node (ref "SW2") (pin "2") (pinfunction "2_2") (pintype "passive"))
      (node (ref "SW3") (pin "1") (pinfunction "1_1") (pintype "passive"))
      (node (ref "U1") (pin "23") (pinfunction "VSS_1_23") (pintype "power_in"))
      (node (ref "U1") (pin "35") (pinfunction "VSS_2_35") (pintype "power_in"))
      (node (ref "U1") (pin "47") (pinfunction "VSS_3_47") (pintype "power_in"))
      (node (ref "U3") (pin "3") (pinfunction "VSSA_3") (pintype "passive"))
      (node (ref "U4") (pin "2") (pinfunction "GND_2") (pintype "passive"))
      (node (ref "USBC1") (pin "0") (pinfunction "0_0") (pintype "passive"))
      (node (ref "USBC1") (pin "A1") (pinfunction "GND_A1") (pintype "passive"))
      (node (ref "USBC1") (pin "A12") (pinfunction "GND_A12") (pintype "passive"))
      (node (ref "USBC1") (pin "B1") (pinfunction "GND_B1") (pintype "passive"))
      (node (ref "USBC1") (pin "B12") (pinfunction "GND_B12") (pintype "passive"))
    )
    (net (code "28") (name "GNDA") (class "Default")
      (node (ref "C38") (pin "1") (pinfunction "1_1") (pintype "passive"))
      (node (ref "C39") (pin "1") (pinfunction "1_1") (pintype "passive"))
      (node (ref "C44") (pin "1") (pinfunction "1_1") (pintype "passive"))
      (node (ref "C46") (pin "1") (pinfunction "1_1") (pintype "passive"))
      (node (ref "C47") (pin "1") (pinfunction "1_1") (pintype "passive"))
      (node (ref "C48") (pin "1") (pinfunction "1_1") (pintype "passive"))
      (node (ref "C55") (pin "1") (pinfunction "1_1") (pintype "passive"))
      (node (ref "C56") (pin "1") (pinfunction "1_1") (pintype "passive"))
      (node (ref "FB7") (pin "2") (pinfunction "2_2") (pintype "passive"))
      (node (ref "U3") (pin "27") (pinfunction "GND_HP_27") (pintype "passive"))
      (node (ref "U3") (pin "36") (pinfunction "AVSS_36") (pintype "passive"))
      (node (ref "U3") (pin "44") (pinfunction "GNDCP_44") (pintype "passive"))
    )
    (net (code "29") (name "GNDRF") (class "Default")
      (node (ref "BK1") (pin "33") (pinfunction "33_33") (pintype "passive"))
      (node (ref "C17") (pin "2") (pinfunction "2_2") (pintype "passive"))
      (node (ref "C18") (pin "2") (pinfunction "2_2") (pintype "passive"))
      (node (ref "C19") (pin "2") (pinfunction "2_2") (pintype "passive"))
      (node (ref "C2") (pin "1") (pinfunction "1_1") (pintype "passive"))
      (node (ref "C20") (pin "2") (pinfunction "2_2") (pintype "passive"))
      (node (ref "C21") (pin "2") (pinfunction "2_2") (pintype "passive"))
      (node (ref "C23") (pin "1") (pinfunction "1_1") (pintype "passive"))
      (node (ref "C24") (pin "2") (pinfunction "2_2") (pintype "passive"))
      (node (ref "C3") (pin "1") (pinfunction "1_1") (pintype "passive"))
      (node (ref "C30") (pin "1") (pinfunction "1_1") (pintype "passive"))
      (node (ref "C31") (pin "1") (pinfunction "1_1") (pintype "passive"))
      (node (ref "C32") (pin "1") (pinfunction "1_1") (pintype "passive"))
      (node (ref "C33") (pin "2") (pinfunction "2_2") (pintype "passive"))
      (node (ref "C34") (pin "2") (pinfunction "2_2") (pintype "passive"))
      (node (ref "C35") (pin "2") (pinfunction "2_2") (pintype "passive"))
      (node (ref "C36") (pin "1") (pinfunction "1_1") (pintype "passive"))
      (node (ref "C5") (pin "1") (pinfunction "1_1") (pintype "passive"))
      (node (ref "C6") (pin "1") (pinfunction "1_1") (pintype "passive"))
      (node (ref "C7") (pin "1") (pinfunction "1_1") (pintype "passive"))
      (node (ref "C8") (pin "1") (pinfunction "1_1") (pintype "passive"))
      (node (ref "FB5") (pin "2") (pinfunction "2_2") (pintype "passive"))
      (node (ref "JP1") (pin "2") (pinfunction "GND_2") (pintype "passive"))
      (node (ref "JP1") (pin "3") (pinfunction "GND_3") (pintype "passive"))
      (node (ref "JP2") (pin "2") (pinfunction "GND_2") (pintype "passive"))
      (node (ref "JP2") (pin "3") (pinfunction "GND_3") (pintype "passive"))
      (node (ref "L5") (pin "1") (pinfunction "1_1") (pintype "passive"))
      (node (ref "R14") (pin "1") (pinfunction "1_1") (pintype "passive"))
      (node (ref "U2") (pin "2") (pinfunction "GND_2") (pintype "passive"))
    )
    (net (code "30") (name "Net-(BK1-EXCN)") (class "Default")
      (node (ref "BK1") (pin "12") (pinfunction "EXCN_12") (pintype "passive"))
      (node (ref "C22") (pin "2") (pinfunction "2_2") (pintype "passive"))
    )
    (net (code "31") (name "Net-(BK1-EXCP)") (class "Default")
      (node (ref "BK1") (pin "11") (pinfunction "EXCP_11") (pintype "passive"))
      (node (ref "C22") (pin "1") (pinfunction "1_1") (pintype "passive"))
    )
    (net (code "32") (name "Net-(BK1-TXON)") (class "Default")
      (node (ref "BK1") (pin "9") (pinfunction "TXON_9") (pintype "passive"))
      (node (ref "C10") (pin "1") (pinfunction "1_1") (pintype "passive"))
      (node (ref "L1") (pin "1") (pinfunction "1_1") (pintype "passive"))
    )
    (net (code "33") (name "Net-(BK1-TXOP)") (class "Default")
      (node (ref "BK1") (pin "10") (pinfunction "TXOP_10") (pintype "passive"))
      (node (ref "C16") (pin "1") (pinfunction "1_1") (pintype "passive"))
      (node (ref "L2") (pin "1") (pinfunction "1_1") (pintype "passive"))
    )
    (net (code "34") (name "Net-(BK1-VCCTX)") (class "Default")
      (node (ref "BK1") (pin "7") (pinfunction "VCCTX_7") (pintype "passive"))
      (node (ref "FB1") (pin "2") (pinfunction "2_2") (pintype "passive"))
    )
    (net (code "35") (name "Net-(BK1-VDDDIG)") (class "Default")
      (node (ref "BK1") (pin "17") (pinfunction "VDDDIG_17") (pintype "passive"))
      (node (ref "C31") (pin "2") (pinfunction "2_2") (pintype "passive"))
    )
    (net (code "36") (name "Net-(BK1-VDDVCO)") (class "Default")
      (node (ref "BK1") (pin "1") (pinfunction "VDDVCO_1") (pintype "passive"))
      (node (ref "C7") (pin "2") (pinfunction "2_2") (pintype "passive"))
    )
    (net (code "37") (name "Net-(BK1-XI)") (class "Default")
      (node (ref "BK1") (pin "31") (pinfunction "XI_31") (pintype "passive"))
      (node (ref "C20") (pin "1") (pinfunction "1_1") (pintype "passive"))
      (node (ref "Y1") (pin "1") (pinfunction "OSC1_1") (pintype "passive"))
    )
    (net (code "38") (name "Net-(BK1-XO)") (class "Default")
      (node (ref "BK1") (pin "30") (pinfunction "XO_30") (pintype "passive"))
      (node (ref "C21") (pin "1") (pinfunction "1_1") (pintype "passive"))
      (node (ref "Y1") (pin "2") (pinfunction "OSC2_2") (pintype "passive"))
    )
    (net (code "39") (name "Net-(C2-Pad2)") (class "Default")
      (node (ref "C2") (pin "2") (pinfunction "2_2") (pintype "passive"))
      (node (ref "C3") (pin "2") (pinfunction "2_2") (pintype "passive"))
      (node (ref "FB1") (pin "1") (pinfunction "1_1") (pintype "passive"))
      (node (ref "L1") (pin "2") (pinfunction "2_2") (pintype "passive"))
      (node (ref "L2") (pin "2") (pinfunction "2_2") (pintype "passive"))
    )
    (net (code "40") (name "Net-(C10-Pad2)") (class "Default")
      (node (ref "C10") (pin "2") (pinfunction "2_2") (pintype "passive"))
      (node (ref "C8") (pin "2") (pinfunction "2_2") (pintype "passive"))
      (node (ref "L4") (pin "2") (pinfunction "2_2") (pintype "passive"))
    )
    (net (code "41") (name "Net-(C15-Pad1)") (class "Default")
      (node (ref "C15") (pin "1") (pinfunction "1_1") (pintype "passive"))
      (node (ref "C16") (pin "2") (pinfunction "2_2") (pintype "passive"))
      (node (ref "L5") (pin "2") (pinfunction "2_2") (pintype "passive"))
    )
    (net (code "42") (name "Net-(C15-Pad2)") (class "Default")
      (node (ref "C15") (pin "2") (pinfunction "2_2") (pintype "passive"))
      (node (ref "C9") (pin "1") (pinfunction "1_1") (pintype "passive"))
      (node (ref "L4") (pin "1") (pinfunction "1_1") (pintype "passive"))
    )
    (net (code "43") (name "Net-(D1-K)") (class "Default")
      (node (ref "D1") (pin "2") (pinfunction "K_2") (pintype "passive"))
      (node (ref "Q2") (pin "3") (pinfunction "C_3") (pintype "passive"))
      (node (ref "R11") (pin "2") (pinfunction "2_2") (pintype "passive"))
    )
    (net (code "44") (name "Net-(IC1-SCL)") (class "Default")
      (node (ref "IC1") (pin "6") (pinfunction "SCL_6") (pintype "input"))
      (node (ref "R24") (pin "1") (pinfunction "1_1") (pintype "passive"))
      (node (ref "U3") (pin "18") (pinfunction "I2C_SCL_18") (pintype "passive"))
    )
    (net (code "45") (name "Net-(IC1-SDA)") (class "Default")
      (node (ref "IC1") (pin "5") (pinfunction "SDA_5") (pintype "bidirectional"))
      (node (ref "R25") (pin "1") (pinfunction "1_1") (pintype "passive"))
      (node (ref "U3") (pin "19") (pinfunction "I2C_SDA_19") (pintype "passive"))
    )
    (net (code "46") (name "Net-(JP1-ANT)") (class "Default")
      (node (ref "C18") (pin "1") (pinfunction "1_1") (pintype "passive"))
      (node (ref "C9") (pin "2") (pinfunction "2_2") (pintype "passive"))
      (node (ref "JP1") (pin "1") (pinfunction "ANT_1") (pintype "passive"))
      (node (ref "L3") (pin "2") (pinfunction "2_2") (pintype "passive"))
    )
    (net (code "47") (name "Net-(JP2-ANT)") (class "Default")
      (node (ref "C17") (pin "1") (pinfunction "1_1") (pintype "passive"))
      (node (ref "JP2") (pin "1") (pinfunction "ANT_1") (pintype "passive"))
      (node (ref "L3") (pin "1") (pinfunction "1_1") (pintype "passive"))
    )
    (net (code "48") (name "Net-(LED1-A)") (class "Default")
      (node (ref "LED1") (pin "1") (pinfunction "A_1") (pintype "passive"))
      (node (ref "R1") (pin "1") (pinfunction "1_1") (pintype "passive"))
    )
    (net (code "49") (name "Net-(LED1-K)") (class "Default")
      (node (ref "LED1") (pin "2") (pinfunction "K_2") (pintype "passive"))
      (node (ref "Q1") (pin "3") (pinfunction "D_3") (pintype "passive"))
    )
    (net (code "50") (name "Net-(LED2-A)") (class "Default")
      (node (ref "LED2") (pin "1") (pinfunction "A_1") (pintype "passive"))
      (node (ref "R2") (pin "1") (pinfunction "1_1") (pintype "passive"))
    )
    (net (code "51") (name "Net-(LED3-A)") (class "Default")
      (node (ref "LED3") (pin "1") (pinfunction "A_1") (pintype "passive"))
      (node (ref "R7") (pin "1") (pinfunction "1_1") (pintype "passive"))
    )
    (net (code "52") (name "Net-(LED4-A)") (class "Default")
      (node (ref "LED4") (pin "1") (pinfunction "A_1") (pintype "passive"))
      (node (ref "R23") (pin "1") (pinfunction "1_1") (pintype "passive"))
    )
    (net (code "53") (name "Net-(Q1-G)") (class "Default")
      (node (ref "Q1") (pin "1") (pinfunction "G_1") (pintype "passive"))
      (node (ref "R4") (pin "1") (pinfunction "1_1") (pintype "passive"))
      (node (ref "R6") (pin "2") (pinfunction "2_2") (pintype "passive"))
    )
    (net (code "54") (name "Net-(Q2-B)") (class "Default")
      (node (ref "Q2") (pin "1") (pinfunction "B_1") (pintype "passive"))
      (node (ref "R12") (pin "2") (pinfunction "2_2") (pintype "passive"))
    )
    (net (code "55") (name "Net-(Q3-B)") (class "Default")
      (node (ref "Q3") (pin "1") (pinfunction "B_1") (pintype "passive"))
      (node (ref "R13") (pin "2") (pinfunction "2_2") (pintype "passive"))
    )
    (net (code "56") (name "Net-(Q3-C)") (class "Default")
      (node (ref "Q3") (pin "3") (pinfunction "C_3") (pintype "passive"))
      (node (ref "R15") (pin "1") (pinfunction "1_1") (pintype "passive"))
    )
    (net (code "57") (name "Net-(U1A-PA3)") (class "Default")
      (node (ref "R4") (pin "2") (pinfunction "2_2") (pintype "passive"))
      (node (ref "U1") (pin "13") (pinfunction "PA3_13") (pintype "bidirectional"))
    )
    (net (code "58") (name "Net-(U1A-PB0)") (class "Default")
      (node (ref "C1") (pin "2") (pinfunction "2_2") (pintype "passive"))
      (node (ref "SW1") (pin "1") (pinfunction "1_1") (pintype "passive"))
      (node (ref "U1") (pin "18") (pinfunction "PB0_18") (pintype "bidirectional"))
    )
    (net (code "59") (name "Net-(U1A-PB1)") (class "Default")
      (node (ref "C4") (pin "2") (pinfunction "2_2") (pintype "passive"))
      (node (ref "SW2") (pin "1") (pinfunction "1_1") (pintype "passive"))
      (node (ref "U1") (pin "19") (pinfunction "PB1_19") (pintype "bidirectional"))
    )
    (net (code "60") (name "Net-(U1A-PB2)") (class "Default")
      (node (ref "R3") (pin "1") (pinfunction "1_1") (pintype "passive"))
      (node (ref "U1") (pin "20") (pinfunction "PB2_20") (pintype "bidirectional"))
    )
    (net (code "61") (name "Net-(U1A-PD0-OSC_IN)") (class "Default")
      (node (ref "C25") (pin "2") (pinfunction "2_2") (pintype "passive"))
      (node (ref "U1") (pin "5") (pinfunction "PD0-OSC_IN_5") (pintype "bidirectional"))
      (node (ref "Y2") (pin "2") (pinfunction "OSC2_2") (pintype "passive"))
    )
    (net (code "62") (name "Net-(U1A-PD1)") (class "Default")
      (node (ref "C29") (pin "2") (pinfunction "2_2") (pintype "passive"))
      (node (ref "U1") (pin "6") (pinfunction "PD1_6") (pintype "bidirectional"))
      (node (ref "Y2") (pin "1") (pinfunction "OSC1_1") (pintype "passive"))
    )
    (net (code "63") (name "Net-(U3-CFLYN)") (class "Default")
      (node (ref "C42") (pin "1") (pinfunction "1_1") (pintype "passive"))
      (node (ref "U3") (pin "43") (pinfunction "CFLYN_43") (pintype "passive"))
    )
    (net (code "64") (name "Net-(U3-CFLYP)") (class "Default")
      (node (ref "C42") (pin "2") (pinfunction "2_2") (pintype "passive"))
      (node (ref "U3") (pin "45") (pinfunction "CFLYP_45") (pintype "passive"))
    )
    (net (code "65") (name "Net-(U3-HPVDD)") (class "Default")
      (node (ref "C46") (pin "2") (pinfunction "2_2") (pintype "passive"))
      (node (ref "U3") (pin "40") (pinfunction "HPVDD_40") (pintype "passive"))
      (node (ref "U3") (pin "41") (pinfunction "VCPP_41") (pintype "passive"))
    )
    (net (code "66") (name "Net-(U3-HPVSS)") (class "Default")
      (node (ref "C44") (pin "2") (pinfunction "2_2") (pintype "passive"))
      (node (ref "U3") (pin "37") (pinfunction "HPVSS_37") (pintype "passive"))
      (node (ref "U3") (pin "42") (pinfunction "VCPN_42") (pintype "passive"))
    )
    (net (code "67") (name "Net-(U3-INSEL)") (class "Default")
      (node (ref "R22") (pin "1") (pinfunction "1_1") (pintype "passive"))
      (node (ref "U3") (pin "9") (pinfunction "INSEL_9") (pintype "passive"))
    )
    (net (code "68") (name "Net-(U3-LEDO)") (class "Default")
      (node (ref "R23") (pin "2") (pinfunction "2_2") (pintype "passive"))
      (node (ref "U3") (pin "8") (pinfunction "LEDO_8") (pintype "passive"))
    )
    (net (code "69") (name "Net-(U3-TEST)") (class "Default")
      (node (ref "R17") (pin "1") (pinfunction "1_1") (pintype "passive"))
      (node (ref "U3") (pin "47") (pinfunction "TEST_47") (pintype "passive"))
    )
    (net (code "70") (name "Net-(U3-V12)") (class "Default")
      (node (ref "C45") (pin "2") (pinfunction "2_2") (pintype "passive"))
      (node (ref "U3") (pin "4") (pinfunction "V12_4") (pintype "passive"))
    )
    (net (code "71") (name "Net-(U3-VMID)") (class "Default")
      (node (ref "C47") (pin "2") (pinfunction "2_2") (pintype "passive"))
      (node (ref "C48") (pin "2") (pinfunction "2_2") (pintype "passive"))
      (node (ref "U3") (pin "35") (pinfunction "VMID_35") (pintype "passive"))
    )
    (net (code "72") (name "Net-(U4-EN)") (class "Default")
      (node (ref "R19") (pin "1") (pinfunction "1_1") (pintype "passive"))
      (node (ref "U4") (pin "3") (pinfunction "EN_3") (pintype "passive"))
    )
    (net (code "73") (name "Net-(USBC1-CC1)") (class "Default")
      (node (ref "R18") (pin "2") (pinfunction "2_2") (pintype "passive"))
      (node (ref "USBC1") (pin "A5") (pinfunction "CC1_A5") (pintype "passive"))
    )
    (net (code "74") (name "Net-(USBC1-CC2)") (class "Default")
      (node (ref "R16") (pin "1") (pinfunction "1_1") (pintype "passive"))
      (node (ref "USBC1") (pin "B5") (pinfunction "CC2_B5") (pintype "passive"))
    )
    (net (code "75") (name "RF3V3") (class "Default")
      (node (ref "BK1") (pin "13") (pinfunction "VCCAUD_13") (pintype "passive"))
      (node (ref "BK1") (pin "16") (pinfunction "VCCDIG_16") (pintype "passive"))
      (node (ref "BK1") (pin "2") (pinfunction "VCCVCO_2") (pintype "passive"))
      (node (ref "BK1") (pin "24") (pinfunction "VCCIF_24") (pintype "passive"))
      (node (ref "BK1") (pin "28") (pinfunction "VCCDVCO_28") (pintype "passive"))
      (node (ref "BK1") (pin "29") (pinfunction "VCCXTAL_29") (pintype "passive"))
      (node (ref "BK1") (pin "32") (pinfunction "VCCPLL_32") (pintype "passive"))
      (node (ref "BK1") (pin "4") (pinfunction "VCCB_4") (pintype "passive"))
      (node (ref "BK1") (pin "8") (pinfunction "VCCPA_8") (pintype "passive"))
      (node (ref "C19") (pin "1") (pinfunction "1_1") (pintype "passive"))
      (node (ref "C23") (pin "2") (pinfunction "2_2") (pintype "passive"))
      (node (ref "C24") (pin "1") (pinfunction "1_1") (pintype "passive"))
      (node (ref "C30") (pin "2") (pinfunction "2_2") (pintype "passive"))
      (node (ref "C32") (pin "2") (pinfunction "2_2") (pintype "passive"))
      (node (ref "C34") (pin "1") (pinfunction "1_1") (pintype "passive"))
      (node (ref "C35") (pin "1") (pinfunction "1_1") (pintype "passive"))
      (node (ref "C36") (pin "2") (pinfunction "2_2") (pintype "passive"))
      (node (ref "C5") (pin "2") (pinfunction "2_2") (pintype "passive"))
      (node (ref "C6") (pin "2") (pinfunction "2_2") (pintype "passive"))
      (node (ref "U2") (pin "5") (pinfunction "VOUT_5") (pintype "passive"))
    )
    (net (code "76") (name "USB_5V") (class "Default")
      (node (ref "C26") (pin "2") (pinfunction "2_2") (pintype "passive"))
      (node (ref "C33") (pin "1") (pinfunction "1_1") (pintype "passive"))
      (node (ref "C51") (pin "1") (pinfunction "1_1") (pintype "passive"))
      (node (ref "C52") (pin "1") (pinfunction "1_1") (pintype "passive"))
      (node (ref "FB4") (pin "1") (pinfunction "1_1") (pintype "passive"))
      (node (ref "R19") (pin "2") (pinfunction "2_2") (pintype "passive"))
      (node (ref "U2") (pin "1") (pinfunction "VIN_1") (pintype "passive"))
      (node (ref "U4") (pin "1") (pinfunction "VIN_1") (pintype "passive"))
    )
    (net (code "77") (name "VBUS") (class "Default")
      (node (ref "C27") (pin "2") (pinfunction "2_2") (pintype "passive"))
      (node (ref "C28") (pin "2") (pinfunction "2_2") (pintype "passive"))
      (node (ref "FB4") (pin "2") (pinfunction "2_2") (pintype "passive"))
      (node (ref "U3") (pin "1") (pinfunction "VBUS_1") (pintype "passive"))
      (node (ref "USBC1") (pin "A4") (pinfunction "VBUS_A4") (pintype "passive"))
      (node (ref "USBC1") (pin "A9") (pinfunction "VBUS_A9") (pintype "passive"))
      (node (ref "USBC1") (pin "B4") (pinfunction "VBUS_B4") (pintype "passive"))
      (node (ref "USBC1") (pin "B9") (pinfunction "VBUS_B9") (pintype "passive"))
    )
    (net (code "78") (name "VDDA") (class "Default")
      (node (ref "C13") (pin "2") (pinfunction "2_2") (pintype "passive"))
      (node (ref "C14") (pin "2") (pinfunction "2_2") (pintype "passive"))
      (node (ref "FB2") (pin "2") (pinfunction "2_2") (pintype "passive"))
      (node (ref "U1") (pin "9") (pinfunction "VDDA_9") (pintype "power_in"))
    )
    (net (code "79") (name "VSSA") (class "Default")
      (node (ref "C13") (pin "1") (pinfunction "1_1") (pintype "passive"))
      (node (ref "C14") (pin "1") (pinfunction "1_1") (pintype "passive"))
      (node (ref "FB3") (pin "2") (pinfunction "2_2") (pintype "passive"))
      (node (ref "U1") (pin "8") (pinfunction "VSSA_8") (pintype "power_in"))
    )
    (net (code "80") (name "unconnected-(BK1-GPIO2-Pad20)") (class "Default")
      (node (ref "BK1") (pin "20") (pinfunction "GPIO2_20") (pintype "passive"))
    )
    (net (code "81") (name "unconnected-(BK1-GPIO4-Pad25)") (class "Default")
      (node (ref "BK1") (pin "25") (pinfunction "GPIO4_25") (pintype "passive+no_connect"))
    )
    (net (code "82") (name "unconnected-(BK1-IRQ-Pad27)") (class "Default")
      (node (ref "BK1") (pin "27") (pinfunction "IRQ_27") (pintype "passive+no_connect"))
    )
    (net (code "83") (name "unconnected-(BK1-MICN-Pad14)") (class "Default")
      (node (ref "BK1") (pin "14") (pinfunction "MICN_14") (pintype "passive+no_connect"))
    )
    (net (code "84") (name "unconnected-(BK1-MICP-Pad15)") (class "Default")
      (node (ref "BK1") (pin "15") (pinfunction "MICP_15") (pintype "passive+no_connect"))
    )
    (net (code "85") (name "unconnected-(BK1-NC-Pad5)") (class "Default")
      (node (ref "BK1") (pin "5") (pinfunction "NC_5") (pintype "passive"))
    )
    (net (code "86") (name "unconnected-(BK1-NC-Pad6)") (class "Default")
      (node (ref "BK1") (pin "6") (pinfunction "NC_6") (pintype "passive"))
    )
    (net (code "87") (name "unconnected-(IC1-WP-Pad7)") (class "Default")
      (node (ref "IC1") (pin "7") (pinfunction "WP_7") (pintype "passive+no_connect"))
    )
    (net (code "88") (name "unconnected-(U1A-PA2-Pad12)") (class "Default")
      (node (ref "U1") (pin "12") (pinfunction "PA2_12") (pintype "bidirectional"))
    )
    (net (code "89") (name "unconnected-(U1A-PA4-Pad14)") (class "Default")
      (node (ref "U1") (pin "14") (pinfunction "PA4_14") (pintype "bidirectional"))
    )
    (net (code "90") (name "unconnected-(U1A-PA7-Pad17)") (class "Default")
      (node (ref "U1") (pin "17") (pinfunction "PA7_17") (pintype "bidirectional"))
    )
    (net (code "91") (name "unconnected-(U1A-PA8-Pad29)") (class "Default")
      (node (ref "U1") (pin "29") (pinfunction "PA8_29") (pintype "bidirectional"))
    )
    (net (code "92") (name "unconnected-(U1A-PA11-Pad32)") (class "Default")
      (node (ref "U1") (pin "32") (pinfunction "PA11_32") (pintype "bidirectional"))
    )
    (net (code "93") (name "unconnected-(U1A-PA15-Pad38)") (class "Default")
      (node (ref "U1") (pin "38") (pinfunction "PA15_38") (pintype "bidirectional"))
    )
    (net (code "94") (name "unconnected-(U1A-PB3-Pad39)") (class "Default")
      (node (ref "U1") (pin "39") (pinfunction "PB3_39") (pintype "bidirectional"))
    )
    (net (code "95") (name "unconnected-(U1A-PB4-Pad40)") (class "Default")
      (node (ref "U1") (pin "40") (pinfunction "PB4_40") (pintype "bidirectional"))
    )
    (net (code "96") (name "unconnected-(U1A-PB5-Pad41)") (class "Default")
      (node (ref "U1") (pin "41") (pinfunction "PB5_41") (pintype "bidirectional"))
    )
    (net (code "97") (name "unconnected-(U1A-PB8-Pad45)") (class "Default")
      (node (ref "U1") (pin "45") (pinfunction "PB8_45") (pintype "bidirectional"))
    )
    (net (code "98") (name "unconnected-(U1A-PB9-Pad46)") (class "Default")
      (node (ref "U1") (pin "46") (pinfunction "PB9_46") (pintype "bidirectional"))
    )
    (net (code "99") (name "unconnected-(U1A-PB10-Pad21)") (class "Default")
      (node (ref "U1") (pin "21") (pinfunction "PB10_21") (pintype "bidirectional"))
    )
    (net (code "100") (name "unconnected-(U1A-PB11-Pad22)") (class "Default")
      (node (ref "U1") (pin "22") (pinfunction "PB11_22") (pintype "bidirectional"))
    )
    (net (code "101") (name "unconnected-(U1A-PB12-Pad25)") (class "Default")
      (node (ref "U1") (pin "25") (pinfunction "PB12_25") (pintype "bidirectional"))
    )
    (net (code "102") (name "unconnected-(U1A-PB13-Pad26)") (class "Default")
      (node (ref "U1") (pin "26") (pinfunction "PB13_26") (pintype "bidirectional"))
    )
    (net (code "103") (name "unconnected-(U1A-PB14-Pad27)") (class "Default")
      (node (ref "U1") (pin "27") (pinfunction "PB14_27") (pintype "bidirectional"))
    )
    (net (code "104") (name "unconnected-(U1A-PB15-Pad28)") (class "Default")
      (node (ref "U1") (pin "28") (pinfunction "PB15_28") (pintype "bidirectional"))
    )
    (net (code "105") (name "unconnected-(U1A-PC13-TAMPER-RTC-Pad2)") (class "Default")
      (node (ref "U1") (pin "2") (pinfunction "PC13-TAMPER-RTC_2") (pintype "bidirectional"))
    )
    (net (code "106") (name "unconnected-(U1A-PC14-OSC32_IN-Pad3)") (class "Default")
      (node (ref "U1") (pin "3") (pinfunction "PC14-OSC32_IN_3") (pintype "bidirectional"))
    )
    (net (code "107") (name "unconnected-(U1A-PC15-OSC32_OUT-Pad4)") (class "Default")
      (node (ref "U1") (pin "4") (pinfunction "PC15-OSC32_OUT_4") (pintype "bidirectional"))
    )
    (net (code "108") (name "unconnected-(U2-NC-Pad4)") (class "Default")
      (node (ref "U2") (pin "4") (pinfunction "NC_4") (pintype "passive+no_connect"))
    )
    (net (code "109") (name "unconnected-(U3-EQ3D_LED-Pad48)") (class "Default")
      (node (ref "U3") (pin "48") (pinfunction "EQ3D_LED_48") (pintype "passive+no_connect"))
    )
    (net (code "110") (name "unconnected-(U3-KEY_RENC_INV-Pad7)") (class "Default")
      (node (ref "U3") (pin "7") (pinfunction "KEY_RENC_INV_7") (pintype "passive+no_connect"))
    )
    (net (code "111") (name "unconnected-(U3-LHPOUT-Pad39)") (class "Default")
      (node (ref "U3") (pin "39") (pinfunction "LHPOUT_39") (pintype "passive+no_connect"))
    )
    (net (code "112") (name "unconnected-(U3-MIC1-Pad29)") (class "Default")
      (node (ref "U3") (pin "29") (pinfunction "MIC1_29") (pintype "passive+no_connect"))
    )
    (net (code "113") (name "unconnected-(U3-MIC1N-Pad31)") (class "Default")
      (node (ref "U3") (pin "31") (pinfunction "MIC1N_31") (pintype "passive+no_connect"))
    )
    (net (code "114") (name "unconnected-(U3-MIC1P-Pad32)") (class "Default")
      (node (ref "U3") (pin "32") (pinfunction "MIC1P_32") (pintype "passive+no_connect"))
    )
    (net (code "115") (name "unconnected-(U3-MIC2P-Pad33)") (class "Default")
      (node (ref "U3") (pin "33") (pinfunction "MIC2P_33") (pintype "passive+no_connect"))
    )
    (net (code "116") (name "unconnected-(U3-MICBIAS-Pad30)") (class "Default")
      (node (ref "U3") (pin "30") (pinfunction "MICBIAS_30") (pintype "passive+no_connect"))
    )
    (net (code "117") (name "unconnected-(U3-MSEL-Pad10)") (class "Default")
      (node (ref "U3") (pin "10") (pinfunction "MSEL_10") (pintype "passive+no_connect"))
    )
    (net (code "118") (name "unconnected-(U3-NEXT_TRACK-Pad20)") (class "Default")
      (node (ref "U3") (pin "20") (pinfunction "NEXT_TRACK_20") (pintype "passive+no_connect"))
    )
    (net (code "119") (name "unconnected-(U3-PALY_PAUSE-Pad22)") (class "Default")
      (node (ref "U3") (pin "22") (pinfunction "PALY_PAUSE_22") (pintype "passive+no_connect"))
    )
    (net (code "120") (name "unconnected-(U3-PLAY_EN-Pad16)") (class "Default")
      (node (ref "U3") (pin "16") (pinfunction "PLAY_EN_16") (pintype "passive+no_connect"))
    )
    (net (code "121") (name "unconnected-(U3-PRE_TACK-Pad21)") (class "Default")
      (node (ref "U3") (pin "21") (pinfunction "PRE_TACK_21") (pintype "passive+no_connect"))
    )
    (net (code "122") (name "unconnected-(U3-REC_EN-Pad17)") (class "Default")
      (node (ref "U3") (pin "17") (pinfunction "REC_EN_17") (pintype "passive+no_connect"))
    )
    (net (code "123") (name "unconnected-(U3-RHPOUT-Pad38)") (class "Default")
      (node (ref "U3") (pin "38") (pinfunction "RHPOUT_38") (pintype "passive+no_connect"))
    )
    (net (code "124") (name "unconnected-(U3-RING2-Pad28)") (class "Default")
      (node (ref "U3") (pin "28") (pinfunction "RING2_28") (pintype "passive+no_connect"))
    )
    (net (code "125") (name "unconnected-(U3-SLEEVE-Pad26)") (class "Default")
      (node (ref "U3") (pin "26") (pinfunction "SLEEVE_26") (pintype "passive+no_connect"))
    )
    (net (code "126") (name "unconnected-(U3-STEREO_MIC-Pad13)") (class "Default")
      (node (ref "U3") (pin "13") (pinfunction "STEREO_MIC_13") (pintype "passive+no_connect"))
    )
    (net (code "127") (name "unconnected-(U3-STOP-Pad24)") (class "Default")
      (node (ref "U3") (pin "24") (pinfunction "STOP_24") (pintype "passive+no_connect"))
    )
    (net (code "128") (name "unconnected-(U3-VOLDN-Pad15)") (class "Default")
      (node (ref "U3") (pin "15") (pinfunction "VOLDN_15") (pintype "passive+no_connect"))
    )
    (net (code "129") (name "unconnected-(U3-VP_MUTE-Pad25)") (class "Default")
      (node (ref "U3") (pin "25") (pinfunction "VP_MUTE_25") (pintype "passive+no_connect"))
    )
    (net (code "130") (name "unconnected-(U3-VR_MUTE-Pad23)") (class "Default")
      (node (ref "U3") (pin "23") (pinfunction "VR_MUTE_23") (pintype "passive+no_connect"))
    )
    (net (code "131") (name "unconnected-(U4-NC-Pad4)") (class "Default")
      (node (ref "U4") (pin "4") (pinfunction "NC_4") (pintype "passive+no_connect"))
    )
    (net (code "132") (name "unconnected-(USBC1-SBU1-PadA8)") (class "Default")
      (node (ref "USBC1") (pin "A8") (pinfunction "SBU1_A8") (pintype "passive"))
    )
    (net (code "133") (name "unconnected-(USBC1-SBU2-PadB8)") (class "Default")
      (node (ref "USBC1") (pin "B8") (pinfunction "SBU2_B8") (pintype "passive"))
    )
  )
)
